# nao_squr_geeezer.net
KiCad netlist of a schematic drawn in EAGLE
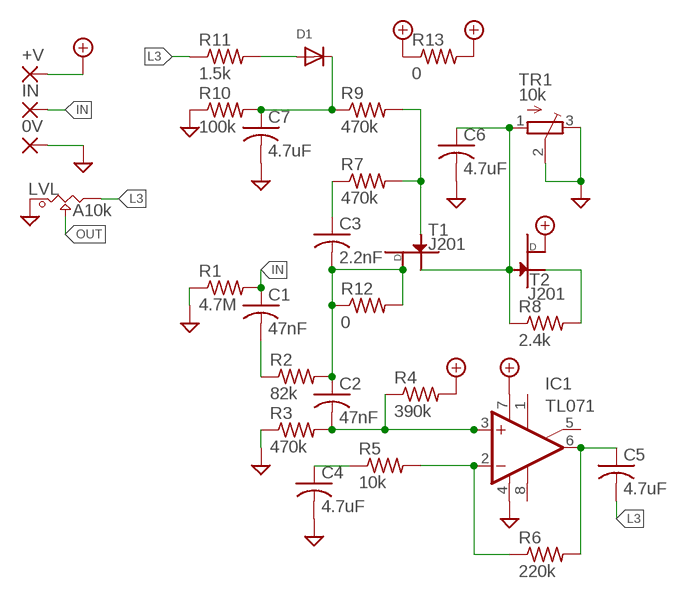
[diagram p0: schematic, sheet 1]

(export (version "E")
  (design (tool "Eeschema 10.0.6"))
  (components
    (comp (ref "+V")
      (value "SMD2")
      (footprint "eagle-import:SMD1,27-2,54")
      (libsource (lib "eagle-import") (part "SMD2"))
    )
    (comp (ref "0V")
      (value "SMD2")
      (footprint "eagle-import:SMD1,27-2,54")
      (libsource (lib "eagle-import") (part "SMD2"))
    )
    (comp (ref "C1")
      (value "47nF")
      (footprint "eagle-import:C0603")
      (libsource (lib "eagle-import") (part "C-USC0603"))
    )
    (comp (ref "C2")
      (value "47nF")
      (footprint "eagle-import:C0603")
      (libsource (lib "eagle-import") (part "C-USC0603"))
    )
    (comp (ref "C3")
      (value "2.2nF")
      (footprint "eagle-import:C0603")
      (libsource (lib "eagle-import") (part "C-USC0603"))
    )
    (comp (ref "C4")
      (value "4.7uF")
      (footprint "eagle-import:C1206")
      (libsource (lib "eagle-import") (part "C-USC1206"))
    )
    (comp (ref "C5")
      (value "4.7uF")
      (footprint "eagle-import:C0805")
      (libsource (lib "eagle-import") (part "C-USC0805"))
    )
    (comp (ref "C6")
      (value "4.7uF")
      (footprint "eagle-import:C0805")
      (libsource (lib "eagle-import") (part "C-USC0805"))
    )
    (comp (ref "C7")
      (value "4.7uF")
      (footprint "eagle-import:C0805")
      (libsource (lib "eagle-import") (part "C-USC0805"))
    )
    (comp (ref "D1")
      (value "DIODESOD-123")
      (footprint "eagle-import:SOD-123")
      (libsource (lib "eagle-import") (part "DIODESOD-123"))
    )
    (comp (ref "IC1")
      (value "TL071")
      (footprint "eagle-import:SO08")
      (libsource (lib "eagle-import") (part "TL071D"))
    )
    (comp (ref "IN")
      (value "SMD2")
      (footprint "eagle-import:SMD1,27-2,54")
      (libsource (lib "eagle-import") (part "SMD2"))
    )
    (comp (ref "LVL")
      (value "A10k")
      (footprint "eagle-import:POT_9MM_SMD")
      (libsource (lib "eagle-import") (part "POT_9MM_SMD"))
    )
    (comp (ref "R1")
      (value "4.7M")
      (footprint "eagle-import:R0603")
      (libsource (lib "eagle-import") (part "R-US_R0603"))
    )
    (comp (ref "R2")
      (value "82k")
      (footprint "eagle-import:R0603")
      (libsource (lib "eagle-import") (part "R-US_R0603"))
    )
    (comp (ref "R3")
      (value "470k")
      (footprint "eagle-import:R0603")
      (libsource (lib "eagle-import") (part "R-US_R0603"))
    )
    (comp (ref "R4")
      (value "390k")
      (footprint "eagle-import:R0603")
      (libsource (lib "eagle-import") (part "R-US_R0603"))
    )
    (comp (ref "R5")
      (value "10k")
      (footprint "eagle-import:R0603")
      (libsource (lib "eagle-import") (part "R-US_R0603"))
    )
    (comp (ref "R6")
      (value "220k")
      (footprint "eagle-import:R0603")
      (libsource (lib "eagle-import") (part "R-US_R0603"))
    )
    (comp (ref "R7")
      (value "470k")
      (footprint "eagle-import:R0603")
      (libsource (lib "eagle-import") (part "R-US_R0603"))
    )
    (comp (ref "R8")
      (value "2.4k")
      (footprint "eagle-import:R0603")
      (libsource (lib "eagle-import") (part "R-US_R0603"))
    )
    (comp (ref "R9")
      (value "470k")
      (footprint "eagle-import:R0603")
      (libsource (lib "eagle-import") (part "R-US_R0603"))
    )
    (comp (ref "R10")
      (value "100k")
      (footprint "eagle-import:R0603")
      (libsource (lib "eagle-import") (part "R-US_R0603"))
    )
    (comp (ref "R11")
      (value "1.5k")
      (footprint "eagle-import:R0603")
      (libsource (lib "eagle-import") (part "R-US_R0603"))
    )
    (comp (ref "R12")
      (value "0")
      (footprint "eagle-import:R0402")
      (libsource (lib "eagle-import") (part "R-US_R0402"))
    )
    (comp (ref "R13")
      (value "0")
      (footprint "eagle-import:R0603")
      (libsource (lib "eagle-import") (part "R-US_R0603"))
    )
    (comp (ref "T1")
      (value "J201")
      (footprint "eagle-import:MMBFJ201")
      (libsource (lib "eagle-import") (part "MMBFJ201"))
    )
    (comp (ref "T2")
      (value "J201")
      (footprint "eagle-import:MMBFJ201")
      (libsource (lib "eagle-import") (part "MMBFJ201"))
    )
    (comp (ref "TR1")
      (value "10k")
      (footprint "eagle-import:TC33X")
      (libsource (lib "eagle-import") (part "TRIMPOTTC33X"))
    )
  )
  (nets
    (net (code "1") (name "+9V") (class "Default")
      (node (ref "+V") (pin "1") (pinfunction "P_1") (pintype "passive"))
      (node (ref "IC1") (pin "7") (pinfunction "V+_7") (pintype "power_in"))
      (node (ref "R13") (pin "1") (pinfunction "1_1") (pintype "passive"))
      (node (ref "R13") (pin "2") (pinfunction "2_2") (pintype "passive"))
      (node (ref "R4") (pin "2") (pinfunction "2_2") (pintype "passive"))
      (node (ref "T2") (pin "D") (pinfunction "D_D") (pintype "bidirectional"))
    )
    (net (code "2") (name "GND") (class "Default")
      (node (ref "0V") (pin "1") (pinfunction "P_1") (pintype "passive"))
      (node (ref "C4") (pin "2") (pinfunction "2_2") (pintype "passive"))
      (node (ref "C6") (pin "2") (pinfunction "2_2") (pintype "passive"))
      (node (ref "C7") (pin "2") (pinfunction "2_2") (pintype "passive"))
      (node (ref "IC1") (pin "4") (pinfunction "V-_4") (pintype "power_in"))
      (node (ref "LVL") (pin "1") (pinfunction "1_1") (pintype "bidirectional"))
      (node (ref "R1") (pin "1") (pinfunction "1_1") (pintype "passive"))
      (node (ref "R10") (pin "1") (pinfunction "1_1") (pintype "passive"))
      (node (ref "R3") (pin "1") (pinfunction "1_1") (pintype "passive"))
      (node (ref "TR1") (pin "2") (pinfunction "S_2") (pintype "passive"))
      (node (ref "TR1") (pin "3") (pinfunction "E_3") (pintype "passive"))
    )
    (net (code "3") (name "IN") (class "Default")
      (node (ref "C1") (pin "1") (pinfunction "1_1") (pintype "passive"))
      (node (ref "IN") (pin "1") (pinfunction "P_1") (pintype "passive"))
      (node (ref "R1") (pin "2") (pinfunction "2_2") (pintype "passive"))
    )
    (net (code "4") (name "L3") (class "Default")
      (node (ref "C5") (pin "2") (pinfunction "2_2") (pintype "passive"))
      (node (ref "LVL") (pin "3") (pinfunction "3_3") (pintype "bidirectional"))
      (node (ref "R11") (pin "1") (pinfunction "1_1") (pintype "passive"))
    )
    (net (code "5") (name "Net-(C1-Pad2)") (class "Default")
      (node (ref "C1") (pin "2") (pinfunction "2_2") (pintype "passive"))
      (node (ref "R2") (pin "1") (pinfunction "1_1") (pintype "passive"))
    )
    (net (code "6") (name "Net-(C2-Pad1)") (class "Default")
      (node (ref "C2") (pin "1") (pinfunction "1_1") (pintype "passive"))
      (node (ref "C3") (pin "2") (pinfunction "2_2") (pintype "passive"))
      (node (ref "R12") (pin "1") (pinfunction "1_1") (pintype "passive"))
      (node (ref "R12") (pin "2") (pinfunction "2_2") (pintype "passive"))
      (node (ref "R2") (pin "2") (pinfunction "2_2") (pintype "passive"))
      (node (ref "T1") (pin "D") (pinfunction "D_D") (pintype "bidirectional"))
    )
    (net (code "7") (name "Net-(C3-Pad1)") (class "Default")
      (node (ref "C3") (pin "1") (pinfunction "1_1") (pintype "passive"))
      (node (ref "R7") (pin "1") (pinfunction "1_1") (pintype "passive"))
    )
    (net (code "8") (name "Net-(C4-Pad1)") (class "Default")
      (node (ref "C4") (pin "1") (pinfunction "1_1") (pintype "passive"))
      (node (ref "R5") (pin "1") (pinfunction "1_1") (pintype "passive"))
    )
    (net (code "9") (name "Net-(C7-Pad1)") (class "Default")
      (node (ref "C7") (pin "1") (pinfunction "1_1") (pintype "passive"))
      (node (ref "D1") (pin "C") (pinfunction "C_C") (pintype "passive"))
      (node (ref "R10") (pin "2") (pinfunction "2_2") (pintype "passive"))
      (node (ref "R9") (pin "1") (pinfunction "1_1") (pintype "passive"))
    )
    (net (code "10") (name "Net-(D1-PadA)") (class "Default")
      (node (ref "D1") (pin "A") (pinfunction "A_A") (pintype "passive"))
      (node (ref "R11") (pin "2") (pinfunction "2_2") (pintype "passive"))
    )
    (net (code "11") (name "Net-(IC1-+IN)") (class "Default")
      (node (ref "C2") (pin "2") (pinfunction "2_2") (pintype "passive"))
      (node (ref "IC1") (pin "3") (pinfunction "+IN_3") (pintype "input"))
      (node (ref "R3") (pin "2") (pinfunction "2_2") (pintype "passive"))
      (node (ref "R4") (pin "1") (pinfunction "1_1") (pintype "passive"))
    )
    (net (code "12") (name "Net-(IC1--IN)") (class "Default")
      (node (ref "IC1") (pin "2") (pinfunction "-IN_2") (pintype "input"))
      (node (ref "R5") (pin "2") (pinfunction "2_2") (pintype "passive"))
      (node (ref "R6") (pin "1") (pinfunction "1_1") (pintype "passive"))
    )
    (net (code "13") (name "Net-(IC1-OUT)") (class "Default")
      (node (ref "C5") (pin "1") (pinfunction "1_1") (pintype "passive"))
      (node (ref "IC1") (pin "6") (pinfunction "OUT_6") (pintype "output"))
      (node (ref "R6") (pin "2") (pinfunction "2_2") (pintype "passive"))
    )
    (net (code "14") (name "Net-(R7-Pad2)") (class "Default")
      (node (ref "R7") (pin "2") (pinfunction "2_2") (pintype "passive"))
      (node (ref "R9") (pin "2") (pinfunction "2_2") (pintype "passive"))
      (node (ref "T1") (pin "G") (pinfunction "G_G") (pintype "bidirectional"))
    )
    (net (code "15") (name "Net-(R8-Pad2)") (class "Default")
      (node (ref "R8") (pin "2") (pinfunction "2_2") (pintype "passive"))
      (node (ref "T2") (pin "S") (pinfunction "S_S") (pintype "bidirectional"))
    )
    (net (code "16") (name "Net-(TR1-A)") (class "Default")
      (node (ref "C6") (pin "1") (pinfunction "1_1") (pintype "passive"))
      (node (ref "R8") (pin "1") (pinfunction "1_1") (pintype "passive"))
      (node (ref "T1") (pin "S") (pinfunction "S_S") (pintype "bidirectional"))
      (node (ref "T2") (pin "G") (pinfunction "G_G") (pintype "bidirectional"))
      (node (ref "TR1") (pin "1") (pinfunction "A_1") (pintype "passive"))
    )
    (net (code "17") (name "OUT") (class "Default")
      (node (ref "LVL") (pin "2") (pinfunction "2_2") (pintype "bidirectional"))
    )
    (net (code "18") (name "unconnected-(IC1-ON1-Pad1)") (class "Default")
      (node (ref "IC1") (pin "1") (pinfunction "ON1_1") (pintype "passive"))
    )
    (net (code "19") (name "unconnected-(IC1-ON2-Pad5)") (class "Default")
      (node (ref "IC1") (pin "5") (pinfunction "ON2_5") (pintype "passive"))
    )
    (net (code "20") (name "unconnected-(IC1-OPT-Pad8)") (class "Default")
      (node (ref "IC1") (pin "8") (pinfunction "OPT_8") (pintype "passive"))
    )
  )
)
